# Schematic.net
KiCad netlist of a schematic drawn in EAGLE
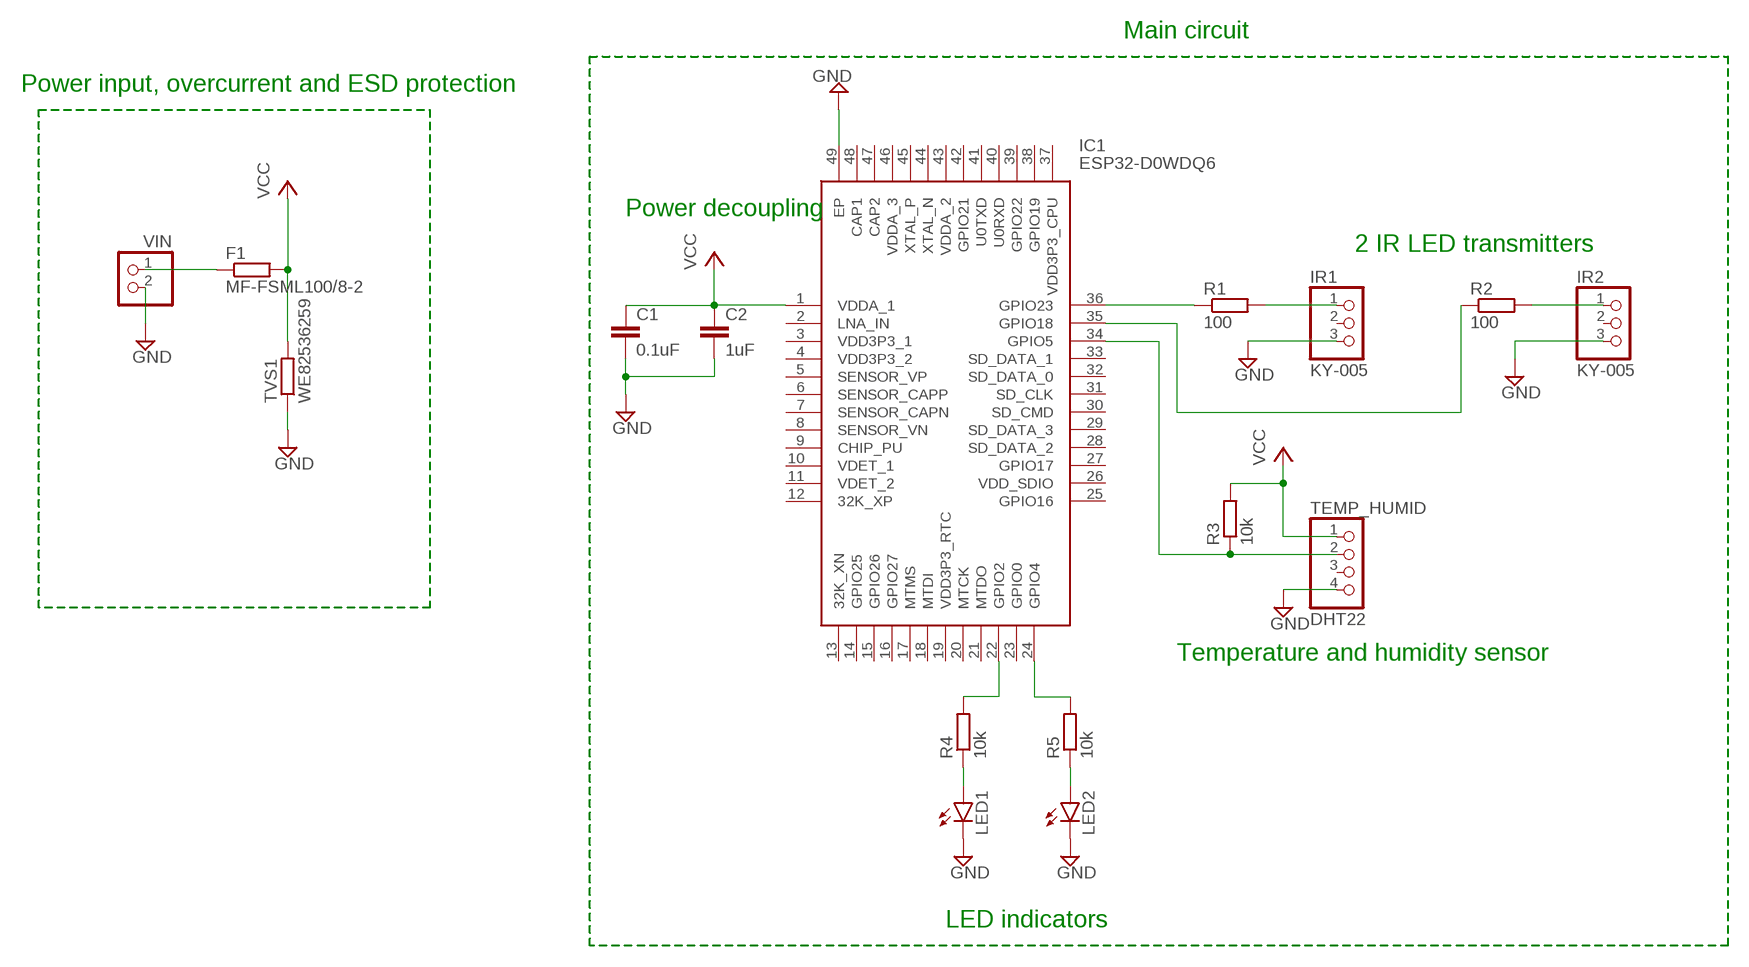
[diagram p0: schematic, sheet 1]

(export (version "E")
  (design (tool "Eeschema 10.0.6"))
  (components
    (comp (ref "C1")
      (value "0.1uF")
      (footprint "eagle-import:C0805")
      (libsource (lib "eagle-import") (part "C-EUC0805"))
    )
    (comp (ref "C2")
      (value "1uF")
      (footprint "eagle-import:C0805")
      (libsource (lib "eagle-import") (part "C-EUC0805"))
    )
    (comp (ref "F1")
      (value "MF-FSML100/8-2")
      (footprint "eagle-import:R0603")
      (libsource (lib "eagle-import") (part "R-EU_R0603"))
    )
    (comp (ref "IC1")
      (value "ESP32-D0WDQ6")
      (footprint "eagle-import:QFN40P600X600X90-49N")
      (fields (field (name "MOUSER_PART_NUMBER") "356-ESP32-D0WDQ6"))
      (libsource (lib "eagle-import") (part "ESP32-D0WDQ6"))
    )
    (comp (ref "IR1")
      (value "KY-005")
      (footprint "eagle-import:1X03")
      (libsource (lib "eagle-import") (part "PINHD-1X3"))
    )
    (comp (ref "IR2")
      (value "KY-005")
      (footprint "eagle-import:1X03")
      (libsource (lib "eagle-import") (part "PINHD-1X3"))
    )
    (comp (ref "LED1")
      (value "LED3MM")
      (footprint "eagle-import:LED3MM")
      (libsource (lib "eagle-import") (part "LED3MM"))
    )
    (comp (ref "LED2")
      (value "LED3MM")
      (footprint "eagle-import:LED3MM")
      (libsource (lib "eagle-import") (part "LED3MM"))
    )
    (comp (ref "R1")
      (value "100")
      (footprint "eagle-import:0207_12")
      (libsource (lib "eagle-import") (part "R-EU_0207/12"))
    )
    (comp (ref "R2")
      (value "100")
      (footprint "eagle-import:0207_12")
      (libsource (lib "eagle-import") (part "R-EU_0207/12"))
    )
    (comp (ref "R3")
      (value "10k")
      (footprint "eagle-import:0207_12")
      (libsource (lib "eagle-import") (part "R-EU_0207/12"))
    )
    (comp (ref "R4")
      (value "10k")
      (footprint "eagle-import:0207_12")
      (libsource (lib "eagle-import") (part "R-EU_0207/12"))
    )
    (comp (ref "R5")
      (value "10k")
      (footprint "eagle-import:0207_12")
      (libsource (lib "eagle-import") (part "R-EU_0207/12"))
    )
    (comp (ref "TEMP_HUMID")
      (value "DHT22")
      (footprint "eagle-import:1X04")
      (libsource (lib "eagle-import") (part "PINHD-1X4"))
    )
    (comp (ref "TVS1")
      (value "WE82536259")
      (footprint "eagle-import:R0603")
      (libsource (lib "eagle-import") (part "R-EU_R0603"))
    )
    (comp (ref "VIN")
      (value "PINHD-1X2")
      (footprint "eagle-import:1X02")
      (libsource (lib "eagle-import") (part "PINHD-1X2"))
    )
  )
  (nets
    (net (code "1") (name "GND") (class "Default")
      (node (ref "C1") (pin "2") (pinfunction "2_2") (pintype "passive"))
      (node (ref "C2") (pin "2") (pinfunction "2_2") (pintype "passive"))
      (node (ref "IC1") (pin "49") (pinfunction "EP_49") (pintype "bidirectional"))
      (node (ref "IR1") (pin "3") (pinfunction "3_3") (pintype "passive"))
      (node (ref "IR2") (pin "3") (pinfunction "3_3") (pintype "passive"))
      (node (ref "LED1") (pin "K") (pinfunction "C_K") (pintype "passive"))
      (node (ref "LED2") (pin "K") (pinfunction "C_K") (pintype "passive"))
      (node (ref "TEMP_HUMID") (pin "4") (pinfunction "4_4") (pintype "passive"))
      (node (ref "TVS1") (pin "1") (pinfunction "1_1") (pintype "passive"))
      (node (ref "VIN") (pin "2") (pinfunction "2_2") (pintype "passive"))
    )
    (net (code "2") (name "Net-(F1-Pad1)") (class "Default")
      (node (ref "F1") (pin "1") (pinfunction "1_1") (pintype "passive"))
      (node (ref "VIN") (pin "1") (pinfunction "1_1") (pintype "passive"))
    )
    (net (code "3") (name "Net-(IC1-GPIO2)") (class "Default")
      (node (ref "IC1") (pin "22") (pinfunction "GPIO2_22") (pintype "bidirectional"))
      (node (ref "R4") (pin "2") (pinfunction "2_2") (pintype "passive"))
    )
    (net (code "4") (name "Net-(IC1-GPIO4)") (class "Default")
      (node (ref "IC1") (pin "24") (pinfunction "GPIO4_24") (pintype "bidirectional"))
      (node (ref "R5") (pin "2") (pinfunction "2_2") (pintype "passive"))
    )
    (net (code "5") (name "Net-(IC1-GPIO5)") (class "Default")
      (node (ref "IC1") (pin "34") (pinfunction "GPIO5_34") (pintype "bidirectional"))
      (node (ref "R3") (pin "1") (pinfunction "1_1") (pintype "passive"))
      (node (ref "TEMP_HUMID") (pin "2") (pinfunction "2_2") (pintype "passive"))
    )
    (net (code "6") (name "Net-(IC1-GPIO18)") (class "Default")
      (node (ref "IC1") (pin "35") (pinfunction "GPIO18_35") (pintype "bidirectional"))
      (node (ref "R2") (pin "1") (pinfunction "1_1") (pintype "passive"))
    )
    (net (code "7") (name "Net-(IC1-GPIO23)") (class "Default")
      (node (ref "IC1") (pin "36") (pinfunction "GPIO23_36") (pintype "bidirectional"))
      (node (ref "R1") (pin "1") (pinfunction "1_1") (pintype "passive"))
    )
    (net (code "8") (name "Net-(IR1-Pad1)") (class "Default")
      (node (ref "IR1") (pin "1") (pinfunction "1_1") (pintype "passive"))
      (node (ref "R1") (pin "2") (pinfunction "2_2") (pintype "passive"))
    )
    (net (code "9") (name "Net-(IR2-Pad1)") (class "Default")
      (node (ref "IR2") (pin "1") (pinfunction "1_1") (pintype "passive"))
      (node (ref "R2") (pin "2") (pinfunction "2_2") (pintype "passive"))
    )
    (net (code "10") (name "Net-(LED1-PadA)") (class "Default")
      (node (ref "LED1") (pin "A") (pinfunction "A_A") (pintype "passive"))
      (node (ref "R4") (pin "1") (pinfunction "1_1") (pintype "passive"))
    )
    (net (code "11") (name "Net-(LED2-PadA)") (class "Default")
      (node (ref "LED2") (pin "A") (pinfunction "A_A") (pintype "passive"))
      (node (ref "R5") (pin "1") (pinfunction "1_1") (pintype "passive"))
    )
    (net (code "12") (name "VCC") (class "Default")
      (node (ref "C1") (pin "1") (pinfunction "1_1") (pintype "passive"))
      (node (ref "C2") (pin "1") (pinfunction "1_1") (pintype "passive"))
      (node (ref "F1") (pin "2") (pinfunction "2_2") (pintype "passive"))
      (node (ref "IC1") (pin "1") (pinfunction "VDDA_1_1") (pintype "bidirectional"))
      (node (ref "R3") (pin "2") (pinfunction "2_2") (pintype "passive"))
      (node (ref "TEMP_HUMID") (pin "1") (pinfunction "1_1") (pintype "passive"))
      (node (ref "TVS1") (pin "2") (pinfunction "2_2") (pintype "passive"))
    )
    (net (code "13") (name "unconnected-(IC1-32K_XN-Pad13)") (class "Default")
      (node (ref "IC1") (pin "13") (pinfunction "32K_XN_13") (pintype "bidirectional"))
    )
    (net (code "14") (name "unconnected-(IC1-32K_XP-Pad12)") (class "Default")
      (node (ref "IC1") (pin "12") (pinfunction "32K_XP_12") (pintype "bidirectional"))
    )
    (net (code "15") (name "unconnected-(IC1-CAP1-Pad48)") (class "Default")
      (node (ref "IC1") (pin "48") (pinfunction "CAP1_48") (pintype "bidirectional"))
    )
    (net (code "16") (name "unconnected-(IC1-CAP2-Pad47)") (class "Default")
      (node (ref "IC1") (pin "47") (pinfunction "CAP2_47") (pintype "bidirectional"))
    )
    (net (code "17") (name "unconnected-(IC1-CHIP_PU-Pad9)") (class "Default")
      (node (ref "IC1") (pin "9") (pinfunction "CHIP_PU_9") (pintype "bidirectional"))
    )
    (net (code "18") (name "unconnected-(IC1-GPIO0-Pad23)") (class "Default")
      (node (ref "IC1") (pin "23") (pinfunction "GPIO0_23") (pintype "bidirectional"))
    )
    (net (code "19") (name "unconnected-(IC1-GPIO16-Pad25)") (class "Default")
      (node (ref "IC1") (pin "25") (pinfunction "GPIO16_25") (pintype "bidirectional"))
    )
    (net (code "20") (name "unconnected-(IC1-GPIO17-Pad27)") (class "Default")
      (node (ref "IC1") (pin "27") (pinfunction "GPIO17_27") (pintype "bidirectional"))
    )
    (net (code "21") (name "unconnected-(IC1-GPIO19-Pad38)") (class "Default")
      (node (ref "IC1") (pin "38") (pinfunction "GPIO19_38") (pintype "bidirectional"))
    )
    (net (code "22") (name "unconnected-(IC1-GPIO21-Pad42)") (class "Default")
      (node (ref "IC1") (pin "42") (pinfunction "GPIO21_42") (pintype "bidirectional"))
    )
    (net (code "23") (name "unconnected-(IC1-GPIO22-Pad39)") (class "Default")
      (node (ref "IC1") (pin "39") (pinfunction "GPIO22_39") (pintype "bidirectional"))
    )
    (net (code "24") (name "unconnected-(IC1-GPIO25-Pad14)") (class "Default")
      (node (ref "IC1") (pin "14") (pinfunction "GPIO25_14") (pintype "bidirectional"))
    )
    (net (code "25") (name "unconnected-(IC1-GPIO26-Pad15)") (class "Default")
      (node (ref "IC1") (pin "15") (pinfunction "GPIO26_15") (pintype "bidirectional"))
    )
    (net (code "26") (name "unconnected-(IC1-GPIO27-Pad16)") (class "Default")
      (node (ref "IC1") (pin "16") (pinfunction "GPIO27_16") (pintype "bidirectional"))
    )
    (net (code "27") (name "unconnected-(IC1-LNA_IN-Pad2)") (class "Default")
      (node (ref "IC1") (pin "2") (pinfunction "LNA_IN_2") (pintype "bidirectional"))
    )
    (net (code "28") (name "unconnected-(IC1-MTCK-Pad20)") (class "Default")
      (node (ref "IC1") (pin "20") (pinfunction "MTCK_20") (pintype "bidirectional"))
    )
    (net (code "29") (name "unconnected-(IC1-MTDI-Pad18)") (class "Default")
      (node (ref "IC1") (pin "18") (pinfunction "MTDI_18") (pintype "bidirectional"))
    )
    (net (code "30") (name "unconnected-(IC1-MTDO-Pad21)") (class "Default")
      (node (ref "IC1") (pin "21") (pinfunction "MTDO_21") (pintype "bidirectional"))
    )
    (net (code "31") (name "unconnected-(IC1-MTMS-Pad17)") (class "Default")
      (node (ref "IC1") (pin "17") (pinfunction "MTMS_17") (pintype "bidirectional"))
    )
    (net (code "32") (name "unconnected-(IC1-SD_CLK-Pad31)") (class "Default")
      (node (ref "IC1") (pin "31") (pinfunction "SD_CLK_31") (pintype "bidirectional"))
    )
    (net (code "33") (name "unconnected-(IC1-SD_CMD-Pad30)") (class "Default")
      (node (ref "IC1") (pin "30") (pinfunction "SD_CMD_30") (pintype "bidirectional"))
    )
    (net (code "34") (name "unconnected-(IC1-SD_DATA_0-Pad32)") (class "Default")
      (node (ref "IC1") (pin "32") (pinfunction "SD_DATA_0_32") (pintype "bidirectional"))
    )
    (net (code "35") (name "unconnected-(IC1-SD_DATA_1-Pad33)") (class "Default")
      (node (ref "IC1") (pin "33") (pinfunction "SD_DATA_1_33") (pintype "bidirectional"))
    )
    (net (code "36") (name "unconnected-(IC1-SD_DATA_2-Pad28)") (class "Default")
      (node (ref "IC1") (pin "28") (pinfunction "SD_DATA_2_28") (pintype "bidirectional"))
    )
    (net (code "37") (name "unconnected-(IC1-SD_DATA_3-Pad29)") (class "Default")
      (node (ref "IC1") (pin "29") (pinfunction "SD_DATA_3_29") (pintype "bidirectional"))
    )
    (net (code "38") (name "unconnected-(IC1-SENSOR_CAPN-Pad7)") (class "Default")
      (node (ref "IC1") (pin "7") (pinfunction "SENSOR_CAPN_7") (pintype "bidirectional"))
    )
    (net (code "39") (name "unconnected-(IC1-SENSOR_CAPP-Pad6)") (class "Default")
      (node (ref "IC1") (pin "6") (pinfunction "SENSOR_CAPP_6") (pintype "bidirectional"))
    )
    (net (code "40") (name "unconnected-(IC1-SENSOR_VN-Pad8)") (class "Default")
      (node (ref "IC1") (pin "8") (pinfunction "SENSOR_VN_8") (pintype "bidirectional"))
    )
    (net (code "41") (name "unconnected-(IC1-SENSOR_VP-Pad5)") (class "Default")
      (node (ref "IC1") (pin "5") (pinfunction "SENSOR_VP_5") (pintype "bidirectional"))
    )
    (net (code "42") (name "unconnected-(IC1-U0RXD-Pad40)") (class "Default")
      (node (ref "IC1") (pin "40") (pinfunction "U0RXD_40") (pintype "bidirectional"))
    )
    (net (code "43") (name "unconnected-(IC1-U0TXD-Pad41)") (class "Default")
      (node (ref "IC1") (pin "41") (pinfunction "U0TXD_41") (pintype "bidirectional"))
    )
    (net (code "44") (name "unconnected-(IC1-VDD3P3_1-Pad3)") (class "Default")
      (node (ref "IC1") (pin "3") (pinfunction "VDD3P3_1_3") (pintype "bidirectional"))
    )
    (net (code "45") (name "unconnected-(IC1-VDD3P3_2-Pad4)") (class "Default")
      (node (ref "IC1") (pin "4") (pinfunction "VDD3P3_2_4") (pintype "bidirectional"))
    )
    (net (code "46") (name "unconnected-(IC1-VDD3P3_CPU-Pad37)") (class "Default")
      (node (ref "IC1") (pin "37") (pinfunction "VDD3P3_CPU_37") (pintype "bidirectional"))
    )
    (net (code "47") (name "unconnected-(IC1-VDD3P3_RTC-Pad19)") (class "Default")
      (node (ref "IC1") (pin "19") (pinfunction "VDD3P3_RTC_19") (pintype "bidirectional"))
    )
    (net (code "48") (name "unconnected-(IC1-VDDA_2-Pad43)") (class "Default")
      (node (ref "IC1") (pin "43") (pinfunction "VDDA_2_43") (pintype "bidirectional"))
    )
    (net (code "49") (name "unconnected-(IC1-VDDA_3-Pad46)") (class "Default")
      (node (ref "IC1") (pin "46") (pinfunction "VDDA_3_46") (pintype "bidirectional"))
    )
    (net (code "50") (name "unconnected-(IC1-VDD_SDIO-Pad26)") (class "Default")
      (node (ref "IC1") (pin "26") (pinfunction "VDD_SDIO_26") (pintype "bidirectional"))
    )
    (net (code "51") (name "unconnected-(IC1-VDET_1-Pad10)") (class "Default")
      (node (ref "IC1") (pin "10") (pinfunction "VDET_1_10") (pintype "bidirectional"))
    )
    (net (code "52") (name "unconnected-(IC1-VDET_2-Pad11)") (class "Default")
      (node (ref "IC1") (pin "11") (pinfunction "VDET_2_11") (pintype "bidirectional"))
    )
    (net (code "53") (name "unconnected-(IC1-XTAL_N-Pad44)") (class "Default")
      (node (ref "IC1") (pin "44") (pinfunction "XTAL_N_44") (pintype "bidirectional"))
    )
    (net (code "54") (name "unconnected-(IC1-XTAL_P-Pad45)") (class "Default")
      (node (ref "IC1") (pin "45") (pinfunction "XTAL_P_45") (pintype "bidirectional"))
    )
    (net (code "55") (name "unconnected-(IR1-Pad2)") (class "Default")
      (node (ref "IR1") (pin "2") (pinfunction "2_2") (pintype "passive"))
    )
    (net (code "56") (name "unconnected-(IR2-Pad2)") (class "Default")
      (node (ref "IR2") (pin "2") (pinfunction "2_2") (pintype "passive"))
    )
    (net (code "57") (name "unconnected-(TEMP_HUMID-Pad3)") (class "Default")
      (node (ref "TEMP_HUMID") (pin "3") (pinfunction "3_3") (pintype "passive"))
    )
  )
)
